# Logo_led.net
KiCad netlist of a schematic drawn in Altium Designer
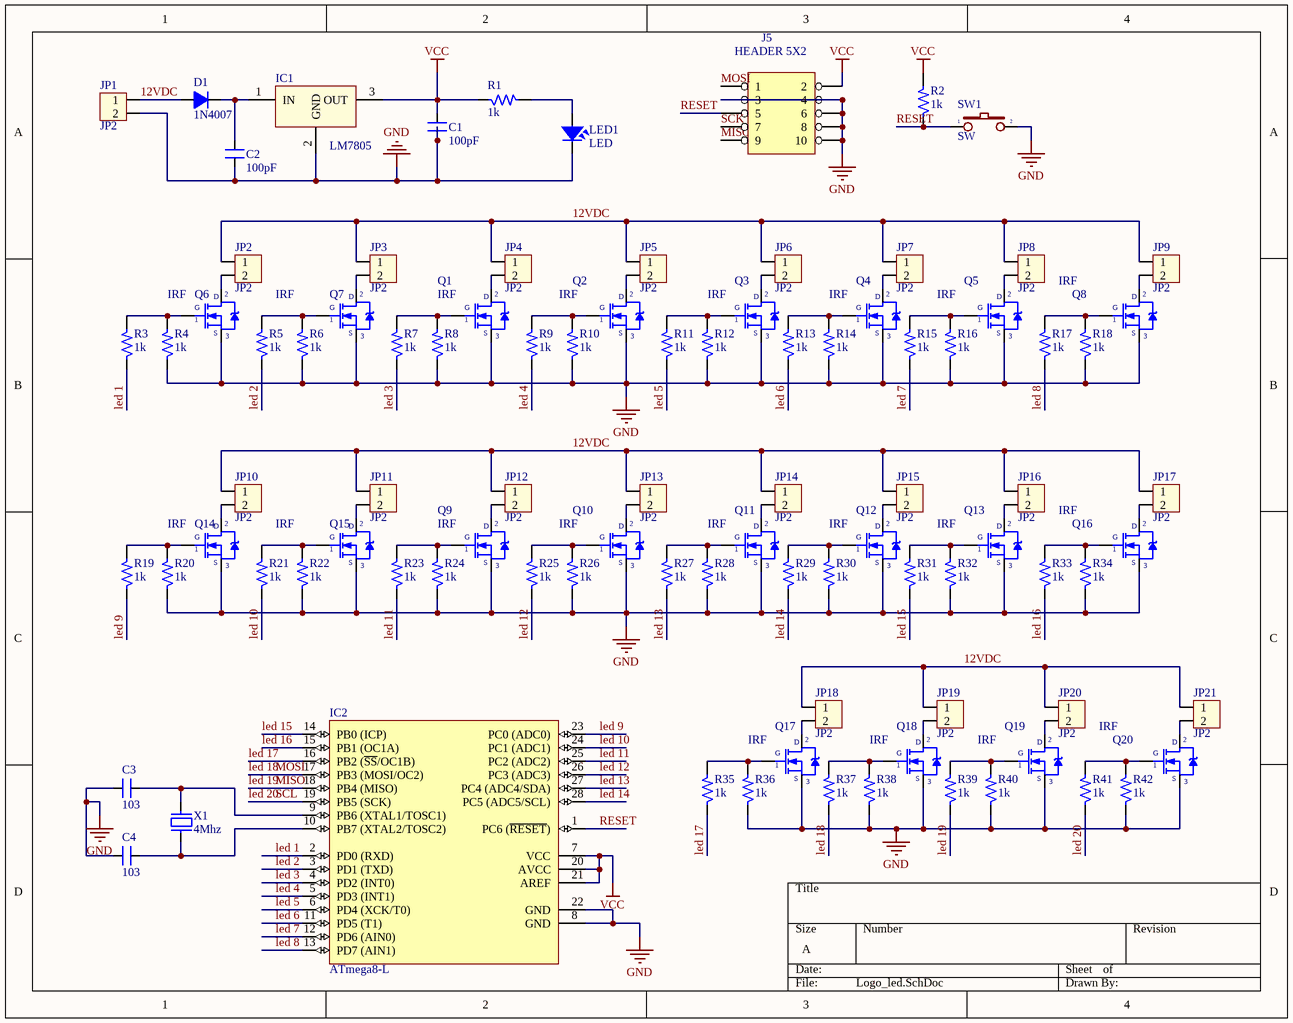
[diagram p0: Logo_led.SchDoc]

(export (version "E")
  (design (tool "Eeschema 10.0.6"))
  (components
    (comp (ref "C1")
      (value "100pF")
      (footprint "CN1")
      (description "Cap np  1pF - 472pF")
      (libsource (lib "syhaunguyen") (part "CN1"))
    )
    (comp (ref "C2")
      (value "100pF")
      (footprint "CN1")
      (description "Cap np  1pF - 472pF")
      (libsource (lib "syhaunguyen") (part "CN1"))
    )
    (comp (ref "C3")
      (value "103")
      (footprint "SM-0805")
      (description "Cap SMD")
      (libsource (lib "syhaunguyen") (part "CM"))
    )
    (comp (ref "C4")
      (value "103")
      (footprint "SM-0805")
      (description "Cap SMD")
      (libsource (lib "syhaunguyen") (part "CM"))
    )
    (comp (ref "D1")
      (value "1N4007")
      (footprint "D1A")
      (description "Diode 1A")
      (libsource (lib "syhaunguyen") (part "D1A"))
    )
    (comp (ref "IC1")
      (value "LM7805")
      (footprint "QTO-220")
      (description "On ap +, from + 5 to + 24VDC")
      (libsource (lib "syhaunguyen") (part "LM78xx"))
    )
    (comp (ref "IC2")
      (value "ATmega8-L")
      (footprint "DIP28/W0.3")
      (description "8-Bit AVR Microcontroller with 8K Bytes of In-System Programmable Flash Memory")
      (libsource (lib "syhaunguyen") (part "ATmega8-L"))
    )
    (comp (ref "J5") (value "HEADER 5X2") (footprint "IDC10") (libsource (lib "*") (part "HEADER 5X2")))
    (comp (ref "JP1")
      (value "JP2")
      (footprint "CON2")
      (description "Connector 2")
      (libsource (lib "") (part "Con2_1"))
    )
    (comp (ref "JP2")
      (value "JP2")
      (footprint "CON2")
      (description "Connector 2")
      (libsource (lib "syhaunguyen") (part "Con2"))
    )
    (comp (ref "JP3")
      (value "JP2")
      (footprint "CON2")
      (description "Connector 2")
      (libsource (lib "syhaunguyen") (part "Con2"))
    )
    (comp (ref "JP4")
      (value "JP2")
      (footprint "CON2")
      (description "Connector 2")
      (libsource (lib "syhaunguyen") (part "Con2"))
    )
    (comp (ref "JP5")
      (value "JP2")
      (footprint "CON2")
      (description "Connector 2")
      (libsource (lib "syhaunguyen") (part "Con2"))
    )
    (comp (ref "JP6")
      (value "JP2")
      (footprint "CON2")
      (description "Connector 2")
      (libsource (lib "syhaunguyen") (part "Con2"))
    )
    (comp (ref "JP7")
      (value "JP2")
      (footprint "CON2")
      (description "Connector 2")
      (libsource (lib "syhaunguyen") (part "Con2"))
    )
    (comp (ref "JP8")
      (value "JP2")
      (footprint "CON2")
      (description "Connector 2")
      (libsource (lib "syhaunguyen") (part "Con2"))
    )
    (comp (ref "JP9")
      (value "JP2")
      (footprint "CON2")
      (description "Connector 2")
      (libsource (lib "syhaunguyen") (part "Con2"))
    )
    (comp (ref "JP10")
      (value "JP2")
      (footprint "CON2")
      (description "Connector 2")
      (libsource (lib "syhaunguyen") (part "Con2"))
    )
    (comp (ref "JP11")
      (value "JP2")
      (footprint "CON2")
      (description "Connector 2")
      (libsource (lib "syhaunguyen") (part "Con2"))
    )
    (comp (ref "JP12")
      (value "JP2")
      (footprint "CON2")
      (description "Connector 2")
      (libsource (lib "syhaunguyen") (part "Con2"))
    )
    (comp (ref "JP13")
      (value "JP2")
      (footprint "CON2")
      (description "Connector 2")
      (libsource (lib "syhaunguyen") (part "Con2"))
    )
    (comp (ref "JP14")
      (value "JP2")
      (footprint "CON2")
      (description "Connector 2")
      (libsource (lib "syhaunguyen") (part "Con2"))
    )
    (comp (ref "JP15")
      (value "JP2")
      (footprint "CON2")
      (description "Connector 2")
      (libsource (lib "syhaunguyen") (part "Con2"))
    )
    (comp (ref "JP16")
      (value "JP2")
      (footprint "CON2")
      (description "Connector 2")
      (libsource (lib "syhaunguyen") (part "Con2"))
    )
    (comp (ref "JP17")
      (value "JP2")
      (footprint "CON2")
      (description "Connector 2")
      (libsource (lib "syhaunguyen") (part "Con2"))
    )
    (comp (ref "JP18")
      (value "JP2")
      (footprint "CON2")
      (description "Connector 2")
      (libsource (lib "syhaunguyen") (part "Con2"))
    )
    (comp (ref "JP19")
      (value "JP2")
      (footprint "CON2")
      (description "Connector 2")
      (libsource (lib "syhaunguyen") (part "Con2"))
    )
    (comp (ref "JP20")
      (value "JP2")
      (footprint "CON2")
      (description "Connector 2")
      (libsource (lib "syhaunguyen") (part "Con2"))
    )
    (comp (ref "JP21")
      (value "JP2")
      (footprint "CON2")
      (description "Connector 2")
      (libsource (lib "syhaunguyen") (part "Con2"))
    )
    (comp (ref "LED1")
      (value "LED")
      (footprint "LED-3")
      (description "LED Single colour Green and Red")
      (libsource (lib "syhaunguyen") (part "LED"))
    )
    (comp (ref "Q1")
      (value "IRF")
      (footprint "QTO-220")
      (description "MOSFET N - CHANNEL 500V - 0.75 - 8A - TO-220")
      (libsource (lib "syhaunguyen") (part "IRF840"))
    )
    (comp (ref "Q2")
      (value "IRF")
      (footprint "QTO-220")
      (description "MOSFET N - CHANNEL 500V - 0.75 - 8A - TO-220")
      (libsource (lib "syhaunguyen") (part "IRF840"))
    )
    (comp (ref "Q3")
      (value "IRF")
      (footprint "QTO-220")
      (description "MOSFET N - CHANNEL 500V - 0.75 - 8A - TO-220")
      (libsource (lib "syhaunguyen") (part "IRF840"))
    )
    (comp (ref "Q4")
      (value "IRF")
      (footprint "QTO-220")
      (description "MOSFET N - CHANNEL 500V - 0.75 - 8A - TO-220")
      (libsource (lib "syhaunguyen") (part "IRF840"))
    )
    (comp (ref "Q5")
      (value "IRF")
      (footprint "QTO-220")
      (description "MOSFET N - CHANNEL 500V - 0.75 - 8A - TO-220")
      (libsource (lib "syhaunguyen") (part "IRF840"))
    )
    (comp (ref "Q6")
      (value "IRF")
      (footprint "QTO-220")
      (description "MOSFET N - CHANNEL 500V - 0.75 - 8A - TO-220")
      (libsource (lib "syhaunguyen") (part "IRF840"))
    )
    (comp (ref "Q7")
      (value "IRF")
      (footprint "QTO-220")
      (description "MOSFET N - CHANNEL 500V - 0.75 - 8A - TO-220")
      (libsource (lib "syhaunguyen") (part "IRF840"))
    )
    (comp (ref "Q8")
      (value "IRF")
      (footprint "QTO-220")
      (description "MOSFET N - CHANNEL 500V - 0.75 - 8A - TO-220")
      (libsource (lib "syhaunguyen") (part "IRF840"))
    )
    (comp (ref "Q9")
      (value "IRF")
      (footprint "QTO-220")
      (description "MOSFET N - CHANNEL 500V - 0.75 - 8A - TO-220")
      (libsource (lib "syhaunguyen") (part "IRF840"))
    )
    (comp (ref "Q10")
      (value "IRF")
      (footprint "QTO-220")
      (description "MOSFET N - CHANNEL 500V - 0.75 - 8A - TO-220")
      (libsource (lib "syhaunguyen") (part "IRF840"))
    )
    (comp (ref "Q11")
      (value "IRF")
      (footprint "QTO-220")
      (description "MOSFET N - CHANNEL 500V - 0.75 - 8A - TO-220")
      (libsource (lib "syhaunguyen") (part "IRF840"))
    )
    (comp (ref "Q12")
      (value "IRF")
      (footprint "QTO-220")
      (description "MOSFET N - CHANNEL 500V - 0.75 - 8A - TO-220")
      (libsource (lib "syhaunguyen") (part "IRF840"))
    )
    (comp (ref "Q13")
      (value "IRF")
      (footprint "QTO-220")
      (description "MOSFET N - CHANNEL 500V - 0.75 - 8A - TO-220")
      (libsource (lib "syhaunguyen") (part "IRF840"))
    )
    (comp (ref "Q14")
      (value "IRF")
      (footprint "QTO-220")
      (description "MOSFET N - CHANNEL 500V - 0.75 - 8A - TO-220")
      (libsource (lib "syhaunguyen") (part "IRF840"))
    )
    (comp (ref "Q15")
      (value "IRF")
      (footprint "QTO-220")
      (description "MOSFET N - CHANNEL 500V - 0.75 - 8A - TO-220")
      (libsource (lib "syhaunguyen") (part "IRF840"))
    )
    (comp (ref "Q16")
      (value "IRF")
      (footprint "QTO-220")
      (description "MOSFET N - CHANNEL 500V - 0.75 - 8A - TO-220")
      (libsource (lib "syhaunguyen") (part "IRF840"))
    )
    (comp (ref "Q17")
      (value "IRF")
      (footprint "QTO-220")
      (description "MOSFET N - CHANNEL 500V - 0.75 - 8A - TO-220")
      (libsource (lib "syhaunguyen") (part "IRF840"))
    )
    (comp (ref "Q18")
      (value "IRF")
      (footprint "QTO-220")
      (description "MOSFET N - CHANNEL 500V - 0.75 - 8A - TO-220")
      (libsource (lib "syhaunguyen") (part "IRF840"))
    )
    (comp (ref "Q19")
      (value "IRF")
      (footprint "QTO-220")
      (description "MOSFET N - CHANNEL 500V - 0.75 - 8A - TO-220")
      (libsource (lib "syhaunguyen") (part "IRF840"))
    )
    (comp (ref "Q20")
      (value "IRF")
      (footprint "QTO-220")
      (description "MOSFET N - CHANNEL 500V - 0.75 - 8A - TO-220")
      (libsource (lib "syhaunguyen") (part "IRF840"))
    )
    (comp (ref "R1")
      (value "1k")
      (footprint "SM-1206")
      (description "Resistor 1/4W")
      (libsource (lib "syhaunguyen") (part "R"))
    )
    (comp (ref "R2")
      (value "1k")
      (footprint "SM-1206")
      (description "Resistor 1/4W")
      (libsource (lib "syhaunguyen") (part "R"))
    )
    (comp (ref "R3")
      (value "1k")
      (footprint "SM-1206")
      (description "Resistor 1/4W")
      (libsource (lib "syhaunguyen") (part "R"))
    )
    (comp (ref "R4")
      (value "1k")
      (footprint "SM-1206")
      (description "Resistor 1/4W")
      (libsource (lib "syhaunguyen") (part "R"))
    )
    (comp (ref "R5")
      (value "1k")
      (footprint "SM-1206")
      (description "Resistor 1/4W")
      (libsource (lib "syhaunguyen") (part "R"))
    )
    (comp (ref "R6")
      (value "1k")
      (footprint "SM-1206")
      (description "Resistor 1/4W")
      (libsource (lib "syhaunguyen") (part "R"))
    )
    (comp (ref "R7")
      (value "1k")
      (footprint "SM-1206")
      (description "Resistor 1/4W")
      (libsource (lib "syhaunguyen") (part "R"))
    )
    (comp (ref "R8")
      (value "1k")
      (footprint "SM-1206")
      (description "Resistor 1/4W")
      (libsource (lib "syhaunguyen") (part "R"))
    )
    (comp (ref "R9")
      (value "1k")
      (footprint "SM-1206")
      (description "Resistor 1/4W")
      (libsource (lib "syhaunguyen") (part "R"))
    )
    (comp (ref "R10")
      (value "1k")
      (footprint "SM-1206")
      (description "Resistor 1/4W")
      (libsource (lib "syhaunguyen") (part "R"))
    )
    (comp (ref "R11")
      (value "1k")
      (footprint "SM-1206")
      (description "Resistor 1/4W")
      (libsource (lib "syhaunguyen") (part "R"))
    )
    (comp (ref "R12")
      (value "1k")
      (footprint "SM-1206")
      (description "Resistor 1/4W")
      (libsource (lib "syhaunguyen") (part "R"))
    )
    (comp (ref "R13")
      (value "1k")
      (footprint "SM-1206")
      (description "Resistor 1/4W")
      (libsource (lib "syhaunguyen") (part "R"))
    )
    (comp (ref "R14")
      (value "1k")
      (footprint "SM-1206")
      (description "Resistor 1/4W")
      (libsource (lib "syhaunguyen") (part "R"))
    )
    (comp (ref "R15")
      (value "1k")
      (footprint "SM-1206")
      (description "Resistor 1/4W")
      (libsource (lib "syhaunguyen") (part "R"))
    )
    (comp (ref "R16")
      (value "1k")
      (footprint "SM-1206")
      (description "Resistor 1/4W")
      (libsource (lib "syhaunguyen") (part "R"))
    )
    (comp (ref "R17")
      (value "1k")
      (footprint "SM-1206")
      (description "Resistor 1/4W")
      (libsource (lib "syhaunguyen") (part "R"))
    )
    (comp (ref "R18")
      (value "1k")
      (footprint "SM-1206")
      (description "Resistor 1/4W")
      (libsource (lib "syhaunguyen") (part "R"))
    )
    (comp (ref "R19")
      (value "1k")
      (footprint "SM-1206")
      (description "Resistor 1/4W")
      (libsource (lib "syhaunguyen") (part "R"))
    )
    (comp (ref "R20")
      (value "1k")
      (footprint "SM-1206")
      (description "Resistor 1/4W")
      (libsource (lib "syhaunguyen") (part "R"))
    )
    (comp (ref "R21")
      (value "1k")
      (footprint "SM-1206")
      (description "Resistor 1/4W")
      (libsource (lib "syhaunguyen") (part "R"))
    )
    (comp (ref "R22")
      (value "1k")
      (footprint "SM-1206")
      (description "Resistor 1/4W")
      (libsource (lib "syhaunguyen") (part "R"))
    )
    (comp (ref "R23")
      (value "1k")
      (footprint "SM-1206")
      (description "Resistor 1/4W")
      (libsource (lib "syhaunguyen") (part "R"))
    )
    (comp (ref "R24")
      (value "1k")
      (footprint "SM-1206")
      (description "Resistor 1/4W")
      (libsource (lib "syhaunguyen") (part "R"))
    )
    (comp (ref "R25")
      (value "1k")
      (footprint "SM-1206")
      (description "Resistor 1/4W")
      (libsource (lib "syhaunguyen") (part "R"))
    )
    (comp (ref "R26")
      (value "1k")
      (footprint "SM-1206")
      (description "Resistor 1/4W")
      (libsource (lib "syhaunguyen") (part "R"))
    )
    (comp (ref "R27")
      (value "1k")
      (footprint "SM-1206")
      (description "Resistor 1/4W")
      (libsource (lib "syhaunguyen") (part "R"))
    )
    (comp (ref "R28")
      (value "1k")
      (footprint "SM-1206")
      (description "Resistor 1/4W")
      (libsource (lib "syhaunguyen") (part "R"))
    )
    (comp (ref "R29")
      (value "1k")
      (footprint "SM-1206")
      (description "Resistor 1/4W")
      (libsource (lib "syhaunguyen") (part "R"))
    )
    (comp (ref "R30")
      (value "1k")
      (footprint "SM-1206")
      (description "Resistor 1/4W")
      (libsource (lib "syhaunguyen") (part "R"))
    )
    (comp (ref "R31")
      (value "1k")
      (footprint "SM-1206")
      (description "Resistor 1/4W")
      (libsource (lib "syhaunguyen") (part "R"))
    )
    (comp (ref "R32")
      (value "1k")
      (footprint "SM-1206")
      (description "Resistor 1/4W")
      (libsource (lib "syhaunguyen") (part "R"))
    )
    (comp (ref "R33")
      (value "1k")
      (footprint "SM-1206")
      (description "Resistor 1/4W")
      (libsource (lib "syhaunguyen") (part "R"))
    )
    (comp (ref "R34")
      (value "1k")
      (footprint "SM-1206")
      (description "Resistor 1/4W")
      (libsource (lib "syhaunguyen") (part "R"))
    )
    (comp (ref "R35")
      (value "1k")
      (footprint "SM-1206")
      (description "Resistor 1/4W")
      (libsource (lib "syhaunguyen") (part "R"))
    )
    (comp (ref "R36")
      (value "1k")
      (footprint "SM-1206")
      (description "Resistor 1/4W")
      (libsource (lib "syhaunguyen") (part "R"))
    )
    (comp (ref "R37")
      (value "1k")
      (footprint "SM-1206")
      (description "Resistor 1/4W")
      (libsource (lib "syhaunguyen") (part "R"))
    )
    (comp (ref "R38")
      (value "1k")
      (footprint "SM-1206")
      (description "Resistor 1/4W")
      (libsource (lib "syhaunguyen") (part "R"))
    )
    (comp (ref "R39")
      (value "1k")
      (footprint "SM-1206")
      (description "Resistor 1/4W")
      (libsource (lib "syhaunguyen") (part "R"))
    )
    (comp (ref "R40")
      (value "1k")
      (footprint "SM-1206")
      (description "Resistor 1/4W")
      (libsource (lib "syhaunguyen") (part "R"))
    )
    (comp (ref "R41")
      (value "1k")
      (footprint "SM-1206")
      (description "Resistor 1/4W")
      (libsource (lib "syhaunguyen") (part "R"))
    )
    (comp (ref "R42")
      (value "1k")
      (footprint "SM-1206")
      (description "Resistor 1/4W")
      (libsource (lib "syhaunguyen") (part "R"))
    )
    (comp (ref "SW1")
      (value "SW")
      (footprint "SW2")
      (description "Switch button 2 pin")
      (libsource (lib "syhaunguyen") (part "SW2"))
    )
    (comp (ref "X1")
      (value "4Mhz")
      (footprint "XT2")
      (description "Crystal For all Crystal 2pin.")
      (libsource (lib "syhaunguyen") (part "XT2"))
    )
  )
  (nets
    (net (code "1") (name "/12VDC") (class "Default")
      (node (ref "D1") (pin "1") (pinfunction "A_1") (pintype "passive"))
      (node (ref "JP1") (pin "1") (pinfunction "1_1") (pintype "passive"))
      (node (ref "JP10") (pin "1") (pinfunction "1_1") (pintype "passive"))
      (node (ref "JP11") (pin "1") (pinfunction "1_1") (pintype "passive"))
      (node (ref "JP12") (pin "1") (pinfunction "1_1") (pintype "passive"))
      (node (ref "JP13") (pin "1") (pinfunction "1_1") (pintype "passive"))
      (node (ref "JP14") (pin "1") (pinfunction "1_1") (pintype "passive"))
      (node (ref "JP15") (pin "1") (pinfunction "1_1") (pintype "passive"))
      (node (ref "JP16") (pin "1") (pinfunction "1_1") (pintype "passive"))
      (node (ref "JP17") (pin "1") (pinfunction "1_1") (pintype "passive"))
      (node (ref "JP18") (pin "1") (pinfunction "1_1") (pintype "passive"))
      (node (ref "JP19") (pin "1") (pinfunction "1_1") (pintype "passive"))
      (node (ref "JP2") (pin "1") (pinfunction "1_1") (pintype "passive"))
      (node (ref "JP20") (pin "1") (pinfunction "1_1") (pintype "passive"))
      (node (ref "JP21") (pin "1") (pinfunction "1_1") (pintype "passive"))
      (node (ref "JP3") (pin "1") (pinfunction "1_1") (pintype "passive"))
      (node (ref "JP4") (pin "1") (pinfunction "1_1") (pintype "passive"))
      (node (ref "JP5") (pin "1") (pinfunction "1_1") (pintype "passive"))
      (node (ref "JP6") (pin "1") (pinfunction "1_1") (pintype "passive"))
      (node (ref "JP7") (pin "1") (pinfunction "1_1") (pintype "passive"))
      (node (ref "JP8") (pin "1") (pinfunction "1_1") (pintype "passive"))
      (node (ref "JP9") (pin "1") (pinfunction "1_1") (pintype "passive"))
    )
    (net (code "2") (name "/MISO") (class "Default")
      (node (ref "IC2") (pin "18") (pinfunction "PB4_(MISO)_18") (pintype "bidirectional"))
      (node (ref "J5") (pin "9") (pinfunction "9_9") (pintype "passive"))
      (node (ref "R39") (pin "1") (pinfunction "1_1") (pintype "passive"))
    )
    (net (code "3") (name "/MOSI") (class "Default")
      (node (ref "IC2") (pin "17") (pinfunction "PB3_(MOSI/OC2)_17") (pintype "bidirectional"))
      (node (ref "J5") (pin "1") (pinfunction "1_1") (pintype "passive"))
      (node (ref "R37") (pin "1") (pinfunction "1_1") (pintype "passive"))
    )
    (net (code "4") (name "/RESET") (class "Default")
      (node (ref "IC2") (pin "1") (pinfunction "PC6_(~{RESET})_1") (pintype "bidirectional"))
      (node (ref "J5") (pin "5") (pinfunction "5_5") (pintype "passive"))
      (node (ref "R2") (pin "1") (pinfunction "1_1") (pintype "passive"))
      (node (ref "SW1") (pin "1") (pinfunction "1_1") (pintype "passive"))
    )
    (net (code "5") (name "/SCK") (class "Default")
      (node (ref "J5") (pin "7") (pinfunction "7_7") (pintype "passive"))
    )
    (net (code "6") (name "/SCL") (class "Default")
      (node (ref "IC2") (pin "19") (pinfunction "PB5_(SCK)_19") (pintype "bidirectional"))
      (node (ref "R41") (pin "1") (pinfunction "1_1") (pintype "passive"))
    )
    (net (code "7") (name "/led 1") (class "Default")
      (node (ref "IC2") (pin "2") (pinfunction "PD0_(RXD)_2") (pintype "bidirectional"))
      (node (ref "R3") (pin "1") (pinfunction "1_1") (pintype "passive"))
    )
    (net (code "8") (name "/led 2") (class "Default")
      (node (ref "IC2") (pin "3") (pinfunction "PD1_(TXD)_3") (pintype "bidirectional"))
      (node (ref "R5") (pin "1") (pinfunction "1_1") (pintype "passive"))
    )
    (net (code "9") (name "/led 3") (class "Default")
      (node (ref "IC2") (pin "4") (pinfunction "PD2_(INT0)_4") (pintype "bidirectional"))
      (node (ref "R7") (pin "1") (pinfunction "1_1") (pintype "passive"))
    )
    (net (code "10") (name "/led 4") (class "Default")
      (node (ref "IC2") (pin "5") (pinfunction "PD3_(INT1)_5") (pintype "bidirectional"))
      (node (ref "R9") (pin "1") (pinfunction "1_1") (pintype "passive"))
    )
    (net (code "11") (name "/led 5") (class "Default")
      (node (ref "IC2") (pin "6") (pinfunction "PD4_(XCK/T0)_6") (pintype "bidirectional"))
      (node (ref "R11") (pin "1") (pinfunction "1_1") (pintype "passive"))
    )
    (net (code "12") (name "/led 6") (class "Default")
      (node (ref "IC2") (pin "11") (pinfunction "PD5_(T1)_11") (pintype "bidirectional"))
      (node (ref "R13") (pin "1") (pinfunction "1_1") (pintype "passive"))
    )
    (net (code "13") (name "/led 7") (class "Default")
      (node (ref "IC2") (pin "12") (pinfunction "PD6_(AIN0)_12") (pintype "bidirectional"))
      (node (ref "R15") (pin "1") (pinfunction "1_1") (pintype "passive"))
    )
    (net (code "14") (name "/led 8") (class "Default")
      (node (ref "IC2") (pin "13") (pinfunction "PD7_(AIN1)_13") (pintype "bidirectional"))
      (node (ref "R17") (pin "1") (pinfunction "1_1") (pintype "passive"))
    )
    (net (code "15") (name "/led 9") (class "Default")
      (node (ref "IC2") (pin "23") (pinfunction "PC0_(ADC0)_23") (pintype "bidirectional"))
      (node (ref "R19") (pin "1") (pinfunction "1_1") (pintype "passive"))
    )
    (net (code "16") (name "/led 10") (class "Default")
      (node (ref "IC2") (pin "24") (pinfunction "PC1_(ADC1)_24") (pintype "bidirectional"))
      (node (ref "R21") (pin "1") (pinfunction "1_1") (pintype "passive"))
    )
    (net (code "17") (name "/led 11") (class "Default")
      (node (ref "IC2") (pin "25") (pinfunction "PC2_(ADC2)_25") (pintype "bidirectional"))
      (node (ref "R23") (pin "1") (pinfunction "1_1") (pintype "passive"))
    )
    (net (code "18") (name "/led 12") (class "Default")
      (node (ref "IC2") (pin "26") (pinfunction "PC3_(ADC3)_26") (pintype "bidirectional"))
      (node (ref "R25") (pin "1") (pinfunction "1_1") (pintype "passive"))
    )
    (net (code "19") (name "/led 13") (class "Default")
      (node (ref "IC2") (pin "27") (pinfunction "PC4_(ADC4/SDA)_27") (pintype "bidirectional"))
      (node (ref "R27") (pin "1") (pinfunction "1_1") (pintype "passive"))
    )
    (net (code "20") (name "/led 14") (class "Default")
      (node (ref "IC2") (pin "28") (pinfunction "PC5_(ADC5/SCL)_28") (pintype "bidirectional"))
      (node (ref "R29") (pin "1") (pinfunction "1_1") (pintype "passive"))
    )
    (net (code "21") (name "/led 15") (class "Default")
      (node (ref "IC2") (pin "14") (pinfunction "PB0_(ICP)_14") (pintype "bidirectional"))
      (node (ref "R31") (pin "1") (pinfunction "1_1") (pintype "passive"))
    )
    (net (code "22") (name "/led 16") (class "Default")
      (node (ref "IC2") (pin "15") (pinfunction "PB1_(OC1A)_15") (pintype "bidirectional"))
      (node (ref "R33") (pin "1") (pinfunction "1_1") (pintype "passive"))
    )
    (net (code "23") (name "/led 17") (class "Default")
      (node (ref "IC2") (pin "16") (pinfunction "PB2_(~{SS}/OC1B)_16") (pintype "bidirectional"))
      (node (ref "R35") (pin "1") (pinfunction "1_1") (pintype "passive"))
    )
    (net (code "24") (name "GND") (class "Default")
      (node (ref "C1") (pin "1") (pinfunction "1_1") (pintype "passive"))
      (node (ref "C2") (pin "1") (pinfunction "1_1") (pintype "passive"))
      (node (ref "C3") (pin "2") (pinfunction "2_2") (pintype "passive"))
      (node (ref "C4") (pin "2") (pinfunction "2_2") (pintype "passive"))
      (node (ref "IC1") (pin "2") (pinfunction "GND_2") (pintype "passive"))
      (node (ref "IC2") (pin "22") (pinfunction "GND_22") (pintype "power_in"))
      (node (ref "IC2") (pin "8") (pinfunction "GND_8") (pintype "power_in"))
      (node (ref "J5") (pin "10") (pinfunction "10_10") (pintype "passive"))
      (node (ref "J5") (pin "3") (pinfunction "3_3") (pintype "passive"))
      (node (ref "J5") (pin "4") (pinfunction "4_4") (pintype "passive"))
      (node (ref "J5") (pin "6") (pinfunction "6_6") (pintype "passive"))
      (node (ref "J5") (pin "8") (pinfunction "8_8") (pintype "passive"))
      (node (ref "JP1") (pin "2") (pinfunction "2_2") (pintype "passive"))
      (node (ref "LED1") (pin "2") (pinfunction "2_2") (pintype "passive"))
      (node (ref "Q1") (pin "3") (pinfunction "S_3") (pintype "passive"))
      (node (ref "Q10") (pin "3") (pinfunction "S_3") (pintype "passive"))
      (node (ref "Q11") (pin "3") (pinfunction "S_3") (pintype "passive"))
      (node (ref "Q12") (pin "3") (pinfunction "S_3") (pintype "passive"))
      (node (ref "Q13") (pin "3") (pinfunction "S_3") (pintype "passive"))
      (node (ref "Q14") (pin "3") (pinfunction "S_3") (pintype "passive"))
      (node (ref "Q15") (pin "3") (pinfunction "S_3") (pintype "passive"))
      (node (ref "Q16") (pin "3") (pinfunction "S_3") (pintype "passive"))
      (node (ref "Q17") (pin "3") (pinfunction "S_3") (pintype "passive"))
      (node (ref "Q18") (pin "3") (pinfunction "S_3") (pintype "passive"))
      (node (ref "Q19") (pin "3") (pinfunction "S_3") (pintype "passive"))
      (node (ref "Q2") (pin "3") (pinfunction "S_3") (pintype "passive"))
      (node (ref "Q20") (pin "3") (pinfunction "S_3") (pintype "passive"))
      (node (ref "Q3") (pin "3") (pinfunction "S_3") (pintype "passive"))
      (node (ref "Q4") (pin "3") (pinfunction "S_3") (pintype "passive"))
      (node (ref "Q5") (pin "3") (pinfunction "S_3") (pintype "passive"))
      (node (ref "Q6") (pin "3") (pinfunction "S_3") (pintype "passive"))
      (node (ref "Q7") (pin "3") (pinfunction "S_3") (pintype "passive"))
      (node (ref "Q8") (pin "3") (pinfunction "S_3") (pintype "passive"))
      (node (ref "Q9") (pin "3") (pinfunction "S_3") (pintype "passive"))
      (node (ref "R10") (pin "1") (pinfunction "1_1") (pintype "passive"))
      (node (ref "R12") (pin "1") (pinfunction "1_1") (pintype "passive"))
      (node (ref "R14") (pin "1") (pinfunction "1_1") (pintype "passive"))
      (node (ref "R16") (pin "1") (pinfunction "1_1") (pintype "passive"))
      (node (ref "R18") (pin "1") (pinfunction "1_1") (pintype "passive"))
      (node (ref "R20") (pin "1") (pinfunction "1_1") (pintype "passive"))
      (node (ref "R22") (pin "1") (pinfunction "1_1") (pintype "passive"))
      (node (ref "R24") (pin "1") (pinfunction "1_1") (pintype "passive"))
      (node (ref "R26") (pin "1") (pinfunction "1_1") (pintype "passive"))
      (node (ref "R28") (pin "1") (pinfunction "1_1") (pintype "passive"))
      (node (ref "R30") (pin "1") (pinfunction "1_1") (pintype "passive"))
      (node (ref "R32") (pin "1") (pinfunction "1_1") (pintype "passive"))
      (node (ref "R34") (pin "1") (pinfunction "1_1") (pintype "passive"))
      (node (ref "R36") (pin "1") (pinfunction "1_1") (pintype "passive"))
      (node (ref "R38") (pin "1") (pinfunction "1_1") (pintype "passive"))
      (node (ref "R4") (pin "1") (pinfunction "1_1") (pintype "passive"))
      (node (ref "R40") (pin "1") (pinfunction "1_1") (pintype "passive"))
      (node (ref "R42") (pin "1") (pinfunction "1_1") (pintype "passive"))
      (node (ref "R6") (pin "1") (pinfunction "1_1") (pintype "passive"))
      (node (ref "R8") (pin "1") (pinfunction "1_1") (pintype "passive"))
      (node (ref "SW1") (pin "2") (pinfunction "2_2") (pintype "passive"))
    )
    (net (code "25") (name "Net-(D1-K)") (class "Default")
      (node (ref "C2") (pin "2") (pinfunction "2_2") (pintype "passive"))
      (node (ref "D1") (pin "2") (pinfunction "K_2") (pintype "passive"))
      (node (ref "IC1") (pin "1") (pinfunction "IN_1") (pintype "passive"))
    )
    (net (code "26") (name "Net-(IC2-PB6_(XTAL1{slash}TOSC1))") (class "Default")
      (node (ref "C3") (pin "1") (pinfunction "1_1") (pintype "passive"))
      (node (ref "IC2") (pin "9") (pinfunction "PB6_(XTAL1/TOSC1)_9") (pintype "bidirectional"))
      (node (ref "X1") (pin "2") (pinfunction "2_2") (pintype "passive"))
    )
    (net (code "27") (name "Net-(IC2-PB7_(XTAL2{slash}TOSC2))") (class "Default")
      (node (ref "C4") (pin "1") (pinfunction "1_1") (pintype "passive"))
      (node (ref "IC2") (pin "10") (pinfunction "PB7_(XTAL2/TOSC2)_10") (pintype "bidirectional"))
      (node (ref "X1") (pin "1") (pinfunction "1_1") (pintype "passive"))
    )
    (net (code "28") (name "Net-(LED1-Pad1)") (class "Default")
      (node (ref "LED1") (pin "1") (pinfunction "1_1") (pintype "passive"))
      (node (ref "R1") (pin "2") (pinfunction "2_2") (pintype "passive"))
    )
    (net (code "29") (name "Net-(Q1-D)") (class "Default")
      (node (ref "JP4") (pin "2") (pinfunction "2_2") (pintype "passive"))
      (node (ref "Q1") (pin "2") (pinfunction "D_2") (pintype "passive"))
    )
    (net (code "30") (name "Net-(Q1-G)") (class "Default")
      (node (ref "Q1") (pin "1") (pinfunction "G_1") (pintype "passive"))
      (node (ref "R7") (pin "2") (pinfunction "2_2") (pintype "passive"))
      (node (ref "R8") (pin "2") (pinfunction "2_2") (pintype "passive"))
    )
    (net (code "31") (name "Net-(Q2-D)") (class "Default")
      (node (ref "JP5") (pin "2") (pinfunction "2_2") (pintype "passive"))
      (node (ref "Q2") (pin "2") (pinfunction "D_2") (pintype "passive"))
    )
    (net (code "32") (name "Net-(Q2-G)") (class "Default")
      (node (ref "Q2") (pin "1") (pinfunction "G_1") (pintype "passive"))
      (node (ref "R10") (pin "2") (pinfunction "2_2") (pintype "passive"))
      (node (ref "R9") (pin "2") (pinfunction "2_2") (pintype "passive"))
    )
    (net (code "33") (name "Net-(Q3-D)") (class "Default")
      (node (ref "JP6") (pin "2") (pinfunction "2_2") (pintype "passive"))
      (node (ref "Q3") (pin "2") (pinfunction "D_2") (pintype "passive"))
    )
    (net (code "34") (name "Net-(Q3-G)") (class "Default")
      (node (ref "Q3") (pin "1") (pinfunction "G_1") (pintype "passive"))
      (node (ref "R11") (pin "2") (pinfunction "2_2") (pintype "passive"))
      (node (ref "R12") (pin "2") (pinfunction "2_2") (pintype "passive"))
    )
    (net (code "35") (name "Net-(Q4-D)") (class "Default")
      (node (ref "JP7") (pin "2") (pinfunction "2_2") (pintype "passive"))
      (node (ref "Q4") (pin "2") (pinfunction "D_2") (pintype "passive"))
    )
    (net (code "36") (name "Net-(Q4-G)") (class "Default")
      (node (ref "Q4") (pin "1") (pinfunction "G_1") (pintype "passive"))
      (node (ref "R13") (pin "2") (pinfunction "2_2") (pintype "passive"))
      (node (ref "R14") (pin "2") (pinfunction "2_2") (pintype "passive"))
    )
    (net (code "37") (name "Net-(Q5-D)") (class "Default")
      (node (ref "JP8") (pin "2") (pinfunction "2_2") (pintype "passive"))
      (node (ref "Q5") (pin "2") (pinfunction "D_2") (pintype "passive"))
    )
    (net (code "38") (name "Net-(Q5-G)") (class "Default")
      (node (ref "Q5") (pin "1") (pinfunction "G_1") (pintype "passive"))
      (node (ref "R15") (pin "2") (pinfunction "2_2") (pintype "passive"))
      (node (ref "R16") (pin "2") (pinfunction "2_2") (pintype "passive"))
    )
    (net (code "39") (name "Net-(Q6-D)") (class "Default")
      (node (ref "JP2") (pin "2") (pinfunction "2_2") (pintype "passive"))
      (node (ref "Q6") (pin "2") (pinfunction "D_2") (pintype "passive"))
    )
    (net (code "40") (name "Net-(Q6-G)") (class "Default")
      (node (ref "Q6") (pin "1") (pinfunction "G_1") (pintype "passive"))
      (node (ref "R3") (pin "2") (pinfunction "2_2") (pintype "passive"))
      (node (ref "R4") (pin "2") (pinfunction "2_2") (pintype "passive"))
    )
    (net (code "41") (name "Net-(Q7-D)") (class "Default")
      (node (ref "JP3") (pin "2") (pinfunction "2_2") (pintype "passive"))
      (node (ref "Q7") (pin "2") (pinfunction "D_2") (pintype "passive"))
    )
    (net (code "42") (name "Net-(Q7-G)") (class "Default")
      (node (ref "Q7") (pin "1") (pinfunction "G_1") (pintype "passive"))
      (node (ref "R5") (pin "2") (pinfunction "2_2") (pintype "passive"))
      (node (ref "R6") (pin "2") (pinfunction "2_2") (pintype "passive"))
    )
    (net (code "43") (name "Net-(Q8-D)") (class "Default")
      (node (ref "JP9") (pin "2") (pinfunction "2_2") (pintype "passive"))
      (node (ref "Q8") (pin "2") (pinfunction "D_2") (pintype "passive"))
    )
    (net (code "44") (name "Net-(Q8-G)") (class "Default")
      (node (ref "Q8") (pin "1") (pinfunction "G_1") (pintype "passive"))
      (node (ref "R17") (pin "2") (pinfunction "2_2") (pintype "passive"))
      (node (ref "R18") (pin "2") (pinfunction "2_2") (pintype "passive"))
    )
    (net (code "45") (name "Net-(Q9-D)") (class "Default")
      (node (ref "JP12") (pin "2") (pinfunction "2_2") (pintype "passive"))
      (node (ref "Q9") (pin "2") (pinfunction "D_2") (pintype "passive"))
    )
    (net (code "46") (name "Net-(Q9-G)") (class "Default")
      (node (ref "Q9") (pin "1") (pinfunction "G_1") (pintype "passive"))
      (node (ref "R23") (pin "2") (pinfunction "2_2") (pintype "passive"))
      (node (ref "R24") (pin "2") (pinfunction "2_2") (pintype "passive"))
    )
    (net (code "47") (name "Net-(Q10-D)") (class "Default")
      (node (ref "JP13") (pin "2") (pinfunction "2_2") (pintype "passive"))
      (node (ref "Q10") (pin "2") (pinfunction "D_2") (pintype "passive"))
    )
    (net (code "48") (name "Net-(Q10-G)") (class "Default")
      (node (ref "Q10") (pin "1") (pinfunction "G_1") (pintype "passive"))
      (node (ref "R25") (pin "2") (pinfunction "2_2") (pintype "passive"))
      (node (ref "R26") (pin "2") (pinfunction "2_2") (pintype "passive"))
    )
    (net (code "49") (name "Net-(Q11-D)") (class "Default")
      (node (ref "JP14") (pin "2") (pinfunction "2_2") (pintype "passive"))
      (node (ref "Q11") (pin "2") (pinfunction "D_2") (pintype "passive"))
    )
    (net (code "50") (name "Net-(Q11-G)") (class "Default")
      (node (ref "Q11") (pin "1") (pinfunction "G_1") (pintype "passive"))
      (node (ref "R27") (pin "2") (pinfunction "2_2") (pintype "passive"))
      (node (ref "R28") (pin "2") (pinfunction "2_2") (pintype "passive"))
    )
    (net (code "51") (name "Net-(Q12-D)") (class "Default")
      (node (ref "JP15") (pin "2") (pinfunction "2_2") (pintype "passive"))
      (node (ref "Q12") (pin "2") (pinfunction "D_2") (pintype "passive"))
    )
    (net (code "52") (name "Net-(Q12-G)") (class "Default")
      (node (ref "Q12") (pin "1") (pinfunction "G_1") (pintype "passive"))
      (node (ref "R29") (pin "2") (pinfunction "2_2") (pintype "passive"))
      (node (ref "R30") (pin "2") (pinfunction "2_2") (pintype "passive"))
    )
    (net (code "53") (name "Net-(Q13-D)") (class "Default")
      (node (ref "JP16") (pin "2") (pinfunction "2_2") (pintype "passive"))
      (node (ref "Q13") (pin "2") (pinfunction "D_2") (pintype "passive"))
    )
    (net (code "54") (name "Net-(Q13-G)") (class "Default")
      (node (ref "Q13") (pin "1") (pinfunction "G_1") (pintype "passive"))
      (node (ref "R31") (pin "2") (pinfunction "2_2") (pintype "passive"))
      (node (ref "R32") (pin "2") (pinfunction "2_2") (pintype "passive"))
    )
    (net (code "55") (name "Net-(Q14-D)") (class "Default")
      (node (ref "JP10") (pin "2") (pinfunction "2_2") (pintype "passive"))
      (node (ref "Q14") (pin "2") (pinfunction "D_2") (pintype "passive"))
    )
    (net (code "56") (name "Net-(Q14-G)") (class "Default")
      (node (ref "Q14") (pin "1") (pinfunction "G_1") (pintype "passive"))
      (node (ref "R19") (pin "2") (pinfunction "2_2") (pintype "passive"))
      (node (ref "R20") (pin "2") (pinfunction "2_2") (pintype "passive"))
    )
    (net (code "57") (name "Net-(Q15-D)") (class "Default")
      (node (ref "JP11") (pin "2") (pinfunction "2_2") (pintype "passive"))
      (node (ref "Q15") (pin "2") (pinfunction "D_2") (pintype "passive"))
    )
    (net (code "58") (name "Net-(Q15-G)") (class "Default")
      (node (ref "Q15") (pin "1") (pinfunction "G_1") (pintype "passive"))
      (node (ref "R21") (pin "2") (pinfunction "2_2") (pintype "passive"))
      (node (ref "R22") (pin "2") (pinfunction "2_2") (pintype "passive"))
    )
    (net (code "59") (name "Net-(Q16-D)") (class "Default")
      (node (ref "JP17") (pin "2") (pinfunction "2_2") (pintype "passive"))
      (node (ref "Q16") (pin "2") (pinfunction "D_2") (pintype "passive"))
    )
    (net (code "60") (name "Net-(Q16-G)") (class "Default")
      (node (ref "Q16") (pin "1") (pinfunction "G_1") (pintype "passive"))
      (node (ref "R33") (pin "2") (pinfunction "2_2") (pintype "passive"))
      (node (ref "R34") (pin "2") (pinfunction "2_2") (pintype "passive"))
    )
    (net (code "61") (name "Net-(Q17-D)") (class "Default")
      (node (ref "JP18") (pin "2") (pinfunction "2_2") (pintype "passive"))
      (node (ref "Q17") (pin "2") (pinfunction "D_2") (pintype "passive"))
    )
    (net (code "62") (name "Net-(Q17-G)") (class "Default")
      (node (ref "Q17") (pin "1") (pinfunction "G_1") (pintype "passive"))
      (node (ref "R35") (pin "2") (pinfunction "2_2") (pintype "passive"))
      (node (ref "R36") (pin "2") (pinfunction "2_2") (pintype "passive"))
    )
    (net (code "63") (name "Net-(Q18-D)") (class "Default")
      (node (ref "JP19") (pin "2") (pinfunction "2_2") (pintype "passive"))
      (node (ref "Q18") (pin "2") (pinfunction "D_2") (pintype "passive"))
    )
    (net (code "64") (name "Net-(Q18-G)") (class "Default")
      (node (ref "Q18") (pin "1") (pinfunction "G_1") (pintype "passive"))
      (node (ref "R37") (pin "2") (pinfunction "2_2") (pintype "passive"))
      (node (ref "R38") (pin "2") (pinfunction "2_2") (pintype "passive"))
    )
    (net (code "65") (name "Net-(Q19-D)") (class "Default")
      (node (ref "JP20") (pin "2") (pinfunction "2_2") (pintype "passive"))
      (node (ref "Q19") (pin "2") (pinfunction "D_2") (pintype "passive"))
    )
    (net (code "66") (name "Net-(Q19-G)") (class "Default")
      (node (ref "Q19") (pin "1") (pinfunction "G_1") (pintype "passive"))
      (node (ref "R39") (pin "2") (pinfunction "2_2") (pintype "passive"))
      (node (ref "R40") (pin "2") (pinfunction "2_2") (pintype "passive"))
    )
    (net (code "67") (name "Net-(Q20-D)") (class "Default")
      (node (ref "JP21") (pin "2") (pinfunction "2_2") (pintype "passive"))
      (node (ref "Q20") (pin "2") (pinfunction "D_2") (pintype "passive"))
    )
    (net (code "68") (name "Net-(Q20-G)") (class "Default")
      (node (ref "Q20") (pin "1") (pinfunction "G_1") (pintype "passive"))
      (node (ref "R41") (pin "2") (pinfunction "2_2") (pintype "passive"))
      (node (ref "R42") (pin "2") (pinfunction "2_2") (pintype "passive"))
    )
    (net (code "69") (name "VCC") (class "Default")
      (node (ref "C1") (pin "2") (pinfunction "2_2") (pintype "passive"))
      (node (ref "IC1") (pin "3") (pinfunction "OUT_3") (pintype "passive"))
      (node (ref "IC2") (pin "20") (pinfunction "AVCC_20") (pintype "power_in"))
      (node (ref "IC2") (pin "21") (pinfunction "AREF_21") (pintype "passive"))
      (node (ref "IC2") (pin "7") (pinfunction "VCC_7") (pintype "power_in"))
      (node (ref "J5") (pin "2") (pinfunction "2_2") (pintype "passive"))
      (node (ref "R1") (pin "1") (pinfunction "1_1") (pintype "passive"))
      (node (ref "R2") (pin "2") (pinfunction "2_2") (pintype "passive"))
    )
  )
)
